# SCH_SibaiCard_2024-10-28.net
KiCad netlist of a schematic drawn in EasyEDA
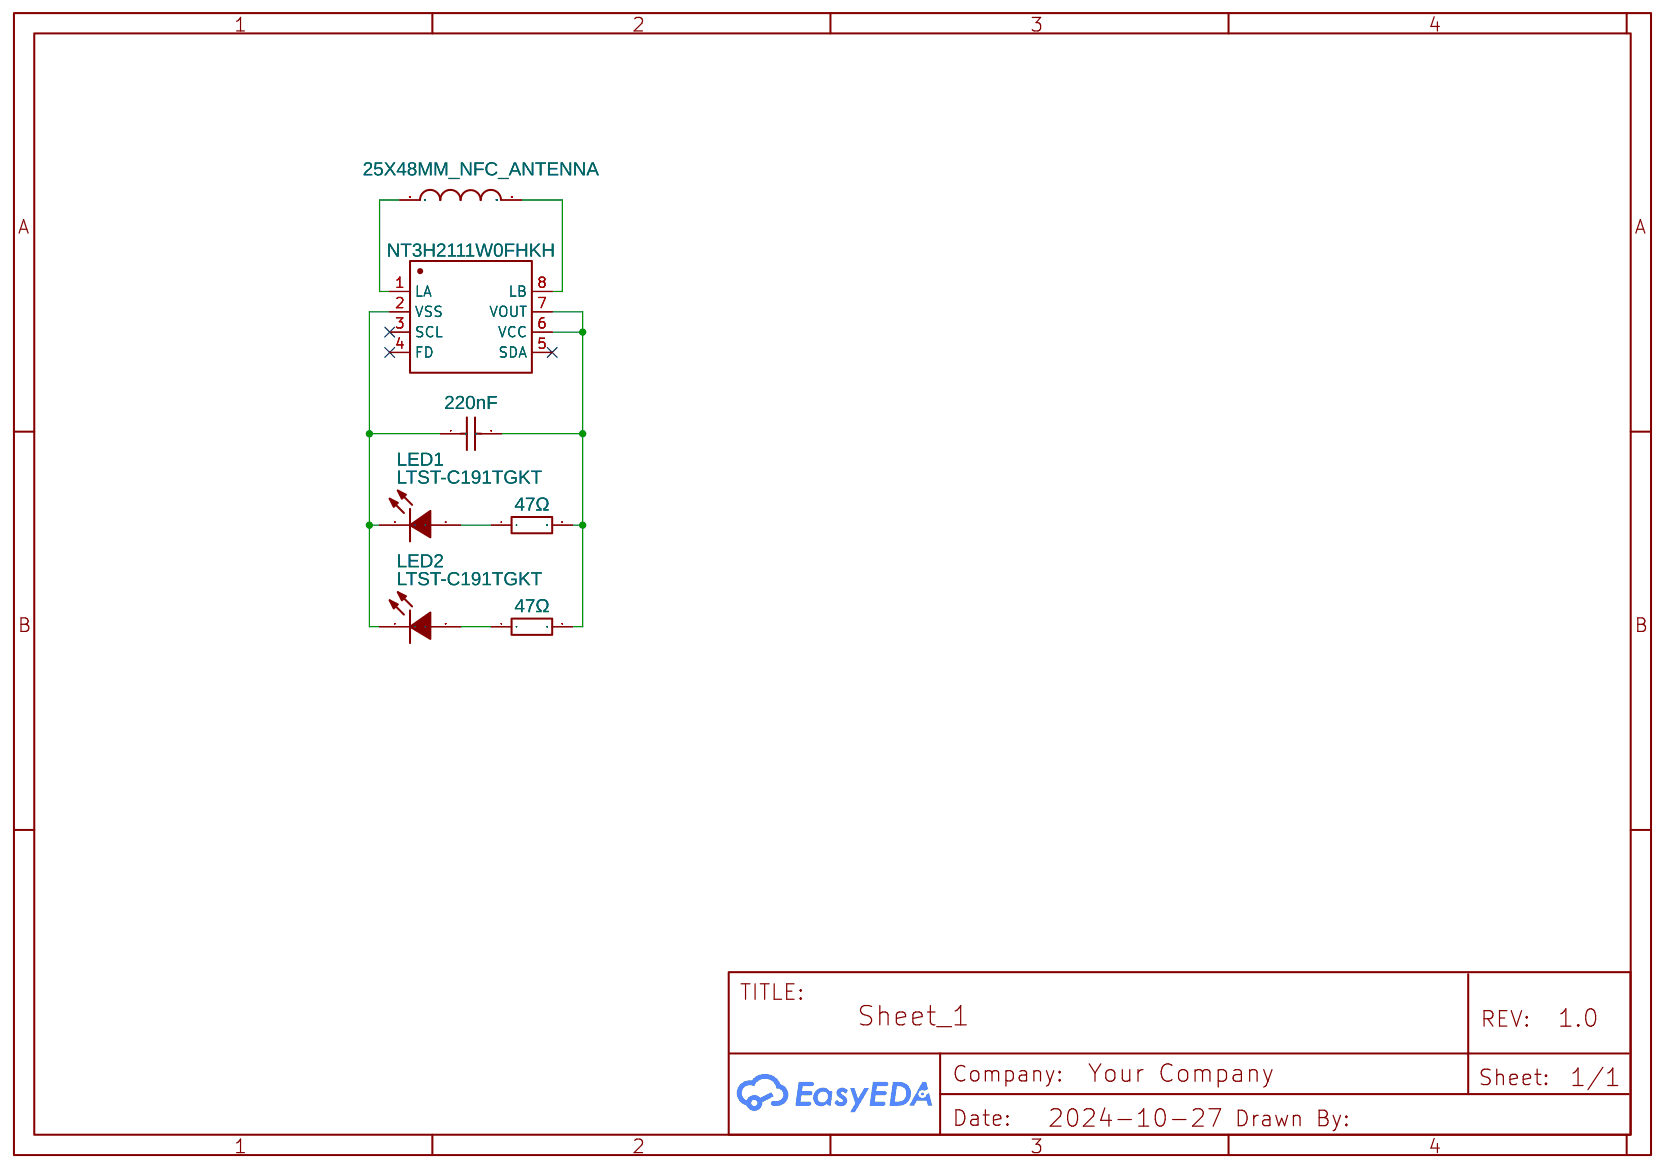
[diagram p0: schematic sheet]

(export (version "E")
  (design (tool "Eeschema 10.0.6"))
  (components
    (comp (ref "1") (value "25X48MM_NFC_ANTENNA") (libsource (lib "") (part "25X48MM_NFC_ANTENNA")))
    (comp (ref "C1")
      (value "220nF")
      (fields
        (field (name "Manufacturer Part") "CL10B224KA8NNNC")
        (field (name "Manufacturer") "SAMSUNG(三星)")
      )
      (libsource (lib "") (part "CL10B224KA8NNNC"))
    )
    (comp (ref "LED1")
      (value "LTST-C191TGKT")
      (fields (field (name "Manufacturer") "LITEON(光宝)"))
      (libsource (lib "") (part "LTST-C191TGKT"))
    )
    (comp (ref "LED2")
      (value "LTST-C191TGKT")
      (fields (field (name "Manufacturer") "LITEON(光宝)"))
      (libsource (lib "") (part "LTST-C191TGKT"))
    )
    (comp (ref "R1")
      (value "47Ω")
      (fields
        (field (name "Manufacturer Part") "0603WAF470JT5E")
        (field (name "Manufacturer") "UNI-ROYAL(厚声)")
      )
      (libsource (lib "") (part "0603WAF470JT5E"))
    )
    (comp (ref "R2")
      (value "47Ω")
      (fields
        (field (name "Manufacturer Part") "0603WAF470JT5E")
        (field (name "Manufacturer") "UNI-ROYAL(厚声)")
      )
      (libsource (lib "") (part "0603WAF470JT5E"))
    )
    (comp (ref "U1")
      (value "NT3H2111W0FHKH")
      (fields (field (name "Manufacturer") "NXP(恩智浦)"))
      (libsource (lib "") (part "NT3H2111W0FHKH"))
    )
  )
  (nets
    (net (code "1") (name "Net-(LED1-+)") (class "Default")
      (node (ref "LED1") (pin "2") (pinfunction "+_2") (pintype "unspecified"))
      (node (ref "R1") (pin "1") (pinfunction "1_1") (pintype "input"))
    )
    (net (code "2") (name "Net-(LED1--)") (class "Default")
      (node (ref "C1") (pin "1") (pinfunction "1_1") (pintype "input"))
      (node (ref "LED1") (pin "1") (pinfunction "-_1") (pintype "unspecified"))
      (node (ref "LED2") (pin "1") (pinfunction "-_1") (pintype "unspecified"))
      (node (ref "U1") (pin "2") (pinfunction "VSS_2") (pintype "unspecified"))
    )
    (net (code "3") (name "Net-(LED2-+)") (class "Default")
      (node (ref "LED2") (pin "2") (pinfunction "+_2") (pintype "unspecified"))
      (node (ref "R2") (pin "1") (pinfunction "1_1") (pintype "input"))
    )
    (net (code "4") (name "Net-(U1-LA)") (class "Default")
      (node (ref "1") (pin "P$1") (pinfunction "P$1_P$1") (pintype "bidirectional"))
      (node (ref "U1") (pin "1") (pinfunction "LA_1") (pintype "unspecified"))
    )
    (net (code "5") (name "Net-(U1-LB)") (class "Default")
      (node (ref "1") (pin "P$2") (pinfunction "P$2_P$2") (pintype "bidirectional"))
      (node (ref "U1") (pin "8") (pinfunction "LB_8") (pintype "unspecified"))
    )
    (net (code "6") (name "Net-(U1-VCC)") (class "Default")
      (node (ref "C1") (pin "2") (pinfunction "2_2") (pintype "input"))
      (node (ref "R1") (pin "2") (pinfunction "2_2") (pintype "input"))
      (node (ref "R2") (pin "2") (pinfunction "2_2") (pintype "input"))
      (node (ref "U1") (pin "6") (pinfunction "VCC_6") (pintype "unspecified"))
      (node (ref "U1") (pin "7") (pinfunction "VOUT_7") (pintype "unspecified"))
    )
    (net (code "7") (name "unconnected-(U1-FD-Pad4)") (class "Default")
      (node (ref "U1") (pin "4") (pinfunction "FD_4") (pintype "unspecified+no_connect"))
    )
    (net (code "8") (name "unconnected-(U1-SCL-Pad3)") (class "Default")
      (node (ref "U1") (pin "3") (pinfunction "SCL_3") (pintype "unspecified+no_connect"))
    )
    (net (code "9") (name "unconnected-(U1-SDA-Pad5)") (class "Default")
      (node (ref "U1") (pin "5") (pinfunction "SDA_5") (pintype "unspecified+no_connect"))
    )
  )
)
